# Power.net
KiCad netlist of a schematic drawn in Altium Designer
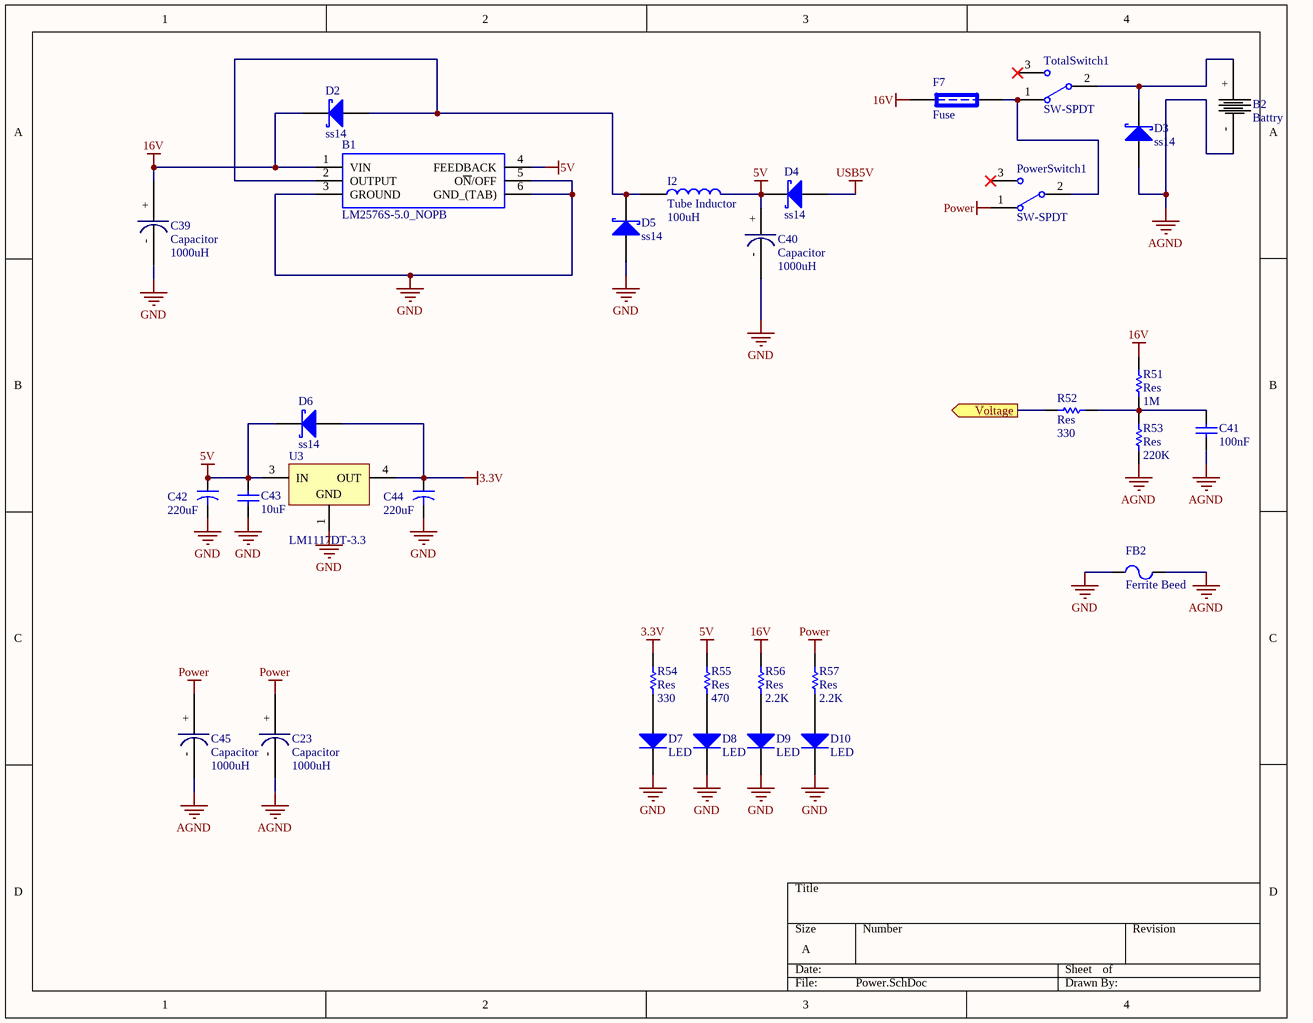
[diagram p0: Power.SchDoc]

(export (version "E")
  (design (tool "Eeschema 10.0.6"))
  (components
    (comp (ref "B1")
      (value "LM2576S-5.0_NOPB")
      (footprint "TO170P1435X465-6N")
      (description "SIMPLE SWITCHER 40V, 3A Low Component Count Step-Down Regulator")
      (fields
        (field (name "RS PART NUMBER") "5333226P")
        (field (name "MANUFACTURER_PART_NUMBER") "LM2576S-5.0/NOPB")
      )
      (libsource (lib "SSL_Power") (part "LM2576S-5.0_NOPB"))
    )
    (comp (ref "B2") (value "Battry") (footprint "Battry") (libsource (lib "SSL_Power") (part "Battry")))
    (comp (ref "C23")
      (value "Capacitor")
      (footprint "DIPCap")
      (fields (field (name "CAPACITANCE") "1000uH"))
      (libsource (lib "SSL_Power") (part "DIPCap"))
    )
    (comp (ref "C39")
      (value "Capacitor")
      (footprint "DIPCap")
      (fields (field (name "CAPACITANCE") "1000uH"))
      (libsource (lib "SSL_Power") (part "DIPCap"))
    )
    (comp (ref "C40")
      (value "Capacitor")
      (footprint "DIPCap")
      (fields (field (name "CAPACITANCE") "1000uH"))
      (libsource (lib "SSL_Power") (part "DIPCap"))
    )
    (comp (ref "C41")
      (value "100nF")
      (footprint "2012[0805]")
      (description "Capacitor")
      (fields (field (name "Comment") "Cap_UP") (field (name "PUBLISHER") "Altium Limited"))
      (libsource (lib "KN2CLib") (part "Cap_UP"))
    )
    (comp (ref "C42")
      (value "220uF")
      (footprint "7343")
      (description "Capacitor")
      (fields (field (name "Comment") "Cap_El") (field (name "PUBLISHER") "Altium Limited"))
      (libsource (lib "KN2CLib") (part "Cap_El"))
    )
    (comp (ref "C43")
      (value "10uF")
      (footprint "2012[0805]")
      (description "Capacitor")
      (fields (field (name "Comment") "Cap_UP") (field (name "PUBLISHER") "Altium Limited"))
      (libsource (lib "KN2CLib") (part "Cap_UP"))
    )
    (comp (ref "C44")
      (value "220uF")
      (footprint "7343")
      (description "Capacitor")
      (fields (field (name "Comment") "Cap_El") (field (name "PUBLISHER") "Altium Limited"))
      (libsource (lib "KN2CLib") (part "Cap_El"))
    )
    (comp (ref "C45")
      (value "Capacitor")
      (footprint "DIPCap")
      (fields (field (name "CAPACITANCE") "1000uH"))
      (libsource (lib "SSL_Power") (part "DIPCap"))
    )
    (comp (ref "D2")
      (value "ss14")
      (footprint "US1m")
      (description "Schottky Diode")
      (fields (field (name "PUBLISHER") "Altium Limited"))
      (libsource (lib "Miscellaneous Devices") (part "D Schottky"))
    )
    (comp (ref "D3")
      (value "ss14")
      (footprint "US1m")
      (description "Schottky Diode")
      (fields (field (name "PUBLISHER") "Altium Limited"))
      (libsource (lib "Miscellaneous Devices") (part "D Schottky"))
    )
    (comp (ref "D4")
      (value "ss14")
      (footprint "US1m")
      (description "Schottky Diode")
      (fields (field (name "PUBLISHER") "Altium Limited"))
      (libsource (lib "Miscellaneous Devices") (part "D Schottky"))
    )
    (comp (ref "D5")
      (value "ss14")
      (footprint "US1m")
      (description "Schottky Diode")
      (fields (field (name "PUBLISHER") "Altium Limited"))
      (libsource (lib "Miscellaneous Devices") (part "D Schottky"))
    )
    (comp (ref "D6")
      (value "ss14")
      (footprint "US1m")
      (description "Schottky Diode")
      (fields (field (name "PUBLISHER") "Altium Limited"))
      (libsource (lib "Miscellaneous Devices") (part "D Schottky"))
    )
    (comp (ref "D7")
      (value "LED")
      (footprint "2012[0805]")
      (description "1 Amp General Purpose Rectifier")
      (fields (field (name "PUBLISHER") "Altium Limited"))
      (libsource (lib "KN2CLib") (part "Diode"))
    )
    (comp (ref "D8")
      (value "LED")
      (footprint "2012[0805]")
      (description "1 Amp General Purpose Rectifier")
      (fields (field (name "PUBLISHER") "Altium Limited"))
      (libsource (lib "KN2CLib") (part "Diode"))
    )
    (comp (ref "D9")
      (value "LED")
      (footprint "2012[0805]")
      (description "1 Amp General Purpose Rectifier")
      (fields (field (name "PUBLISHER") "Altium Limited"))
      (libsource (lib "KN2CLib") (part "Diode"))
    )
    (comp (ref "D10")
      (value "LED")
      (footprint "2012[0805]")
      (description "1 Amp General Purpose Rectifier")
      (fields (field (name "PUBLISHER") "Altium Limited"))
      (libsource (lib "KN2CLib") (part "Diode"))
    )
    (comp (ref "F7")
      (value "Fuse")
      (footprint "3216[1206]")
      (fields (field (name "PUBLISHER") "Altium Limited"))
      (libsource (lib "KN2CLib") (part "Fuse"))
    )
    (comp (ref "FB2")
      (value "Ferrite Beed")
      (footprint "3216[1206]")
      (fields (field (name "PUBLISHER") "Altium Limited"))
      (libsource (lib "KN2CLib") (part "Ferrite Beed"))
    )
    (comp (ref "I2")
      (value "Tube Inductor")
      (footprint "Tube_Inductor")
      (fields (field (name "INDUCTANCE") "100uH"))
      (libsource (lib "SSL_Power") (part "Tube_Inductor"))
    )
    (comp (ref "PowerSwitch1")
      (value "SW-SPDT")
      (footprint "KEYKHRAB")
      (description "SPDT Subminiature Toggle Switch, Right Angle Mounting, Vertical Actuation")
      (fields (field (name "PUBLISHER") "Altium Limited"))
      (libsource (lib "KN2CLib") (part "SW-SPDT"))
    )
    (comp (ref "R51")
      (value "Res")
      (footprint "2012[0805]")
      (description "Semiconductor Resistor")
      (fields (field (name "ALTIUM_VALUE") "1M") (field (name "PUBLISHER") "Altium Limited"))
      (libsource (lib "KN2CLib") (part "Res"))
    )
    (comp (ref "R52")
      (value "Res")
      (footprint "2012[0805]")
      (description "Semiconductor Resistor")
      (fields (field (name "ALTIUM_VALUE") "330") (field (name "PUBLISHER") "Altium Limited"))
      (libsource (lib "KN2CLib") (part "Res"))
    )
    (comp (ref "R53")
      (value "Res")
      (footprint "2012[0805]")
      (description "Semiconductor Resistor")
      (fields (field (name "ALTIUM_VALUE") "220K") (field (name "PUBLISHER") "Altium Limited"))
      (libsource (lib "KN2CLib") (part "Res"))
    )
    (comp (ref "R54")
      (value "Res")
      (footprint "2012[0805]")
      (description "Semiconductor Resistor")
      (fields (field (name "ALTIUM_VALUE") "330") (field (name "PUBLISHER") "Altium Limited"))
      (libsource (lib "KN2CLib") (part "Res"))
    )
    (comp (ref "R55")
      (value "Res")
      (footprint "2012[0805]")
      (description "Semiconductor Resistor")
      (fields (field (name "ALTIUM_VALUE") "470") (field (name "PUBLISHER") "Altium Limited"))
      (libsource (lib "KN2CLib") (part "Res"))
    )
    (comp (ref "R56")
      (value "Res")
      (footprint "2012[0805]")
      (description "Semiconductor Resistor")
      (fields (field (name "ALTIUM_VALUE") "2.2K") (field (name "PUBLISHER") "Altium Limited"))
      (libsource (lib "KN2CLib") (part "Res"))
    )
    (comp (ref "R57")
      (value "Res")
      (footprint "2012[0805]")
      (description "Semiconductor Resistor")
      (fields (field (name "ALTIUM_VALUE") "2.2K") (field (name "PUBLISHER") "Altium Limited"))
      (libsource (lib "KN2CLib") (part "Res"))
    )
    (comp (ref "TotalSwitch1")
      (value "SW-SPDT")
      (footprint "KEYKHRAB")
      (description "SPDT Subminiature Toggle Switch, Right Angle Mounting, Vertical Actuation")
      (fields (field (name "PUBLISHER") "Altium Limited"))
      (libsource (lib "KN2CLib") (part "SW-SPDT"))
    )
    (comp (ref "U3")
      (value "LM1117DT-3.3")
      (footprint "SOT223")
      (description "800mA Low-Dropout Linear Regulator, 3-pin TO-252")
      (fields
        (field (name "MANUFACTURER") "National Semiconductor")
        (field (name "PUBLISHER") "Altium Limited")
      )
      (libsource (lib "NSC LDO") (part "LM1117DT-3.3"))
    )
  )
  (nets
    (net (code "1") (name "/Voltage") (class "Default")
      (node (ref "R52") (pin "1") (pinfunction "1_1") (pintype "passive"))
    )
    (net (code "2") (name "3.3V") (class "Default")
      (node (ref "C44") (pin "1") (pinfunction "1_1") (pintype "passive"))
      (node (ref "D6") (pin "1") (pinfunction "A_1") (pintype "passive"))
      (node (ref "R54") (pin "2") (pinfunction "2_2") (pintype "passive"))
      (node (ref "U3") (pin "4") (pinfunction "OUT_4") (pintype "power_in"))
    )
    (net (code "3") (name "5V") (class "Default")
      (node (ref "B1") (pin "4") (pinfunction "FEEDBACK_4") (pintype "passive"))
      (node (ref "C40") (pin "+") (pinfunction "+_+") (pintype "passive"))
      (node (ref "C42") (pin "1") (pinfunction "1_1") (pintype "passive"))
      (node (ref "C43") (pin "2") (pinfunction "2_2") (pintype "passive"))
      (node (ref "D4") (pin "2") (pinfunction "K_2") (pintype "passive"))
      (node (ref "D6") (pin "2") (pinfunction "K_2") (pintype "passive"))
      (node (ref "I2") (pin "1") (pinfunction "1_1") (pintype "passive"))
      (node (ref "R55") (pin "2") (pinfunction "2_2") (pintype "passive"))
      (node (ref "U3") (pin "3") (pinfunction "IN_3") (pintype "power_in"))
    )
    (net (code "4") (name "16V") (class "Default")
      (node (ref "B1") (pin "1") (pinfunction "VIN_1") (pintype "passive"))
      (node (ref "C39") (pin "+") (pinfunction "+_+") (pintype "passive"))
      (node (ref "D2") (pin "2") (pinfunction "K_2") (pintype "passive"))
      (node (ref "F7") (pin "1") (pinfunction "1_1") (pintype "passive"))
      (node (ref "R51") (pin "2") (pinfunction "2_2") (pintype "passive"))
      (node (ref "R56") (pin "2") (pinfunction "2_2") (pintype "passive"))
    )
    (net (code "5") (name "AGND") (class "Default")
      (node (ref "B2") (pin "-") (pinfunction "-_-") (pintype "passive"))
      (node (ref "C23") (pin "-") (pinfunction "-_-") (pintype "passive"))
      (node (ref "C41") (pin "1") (pinfunction "1_1") (pintype "passive"))
      (node (ref "C45") (pin "-") (pinfunction "-_-") (pintype "passive"))
      (node (ref "D3") (pin "1") (pinfunction "A_1") (pintype "passive"))
      (node (ref "FB2") (pin "2") (pinfunction "2_2") (pintype "passive"))
      (node (ref "R53") (pin "1") (pinfunction "1_1") (pintype "passive"))
    )
    (net (code "6") (name "GND") (class "Default")
      (node (ref "B1") (pin "3") (pinfunction "GROUND_3") (pintype "passive"))
      (node (ref "B1") (pin "5") (pinfunction "O~{N}/OFF_5") (pintype "passive"))
      (node (ref "B1") (pin "6") (pinfunction "GND_(TAB)_6") (pintype "passive"))
      (node (ref "C39") (pin "-") (pinfunction "-_-") (pintype "passive"))
      (node (ref "C40") (pin "-") (pinfunction "-_-") (pintype "passive"))
      (node (ref "C42") (pin "2") (pinfunction "2_2") (pintype "passive"))
      (node (ref "C43") (pin "1") (pinfunction "1_1") (pintype "passive"))
      (node (ref "C44") (pin "2") (pinfunction "2_2") (pintype "passive"))
      (node (ref "D10") (pin "2") (pinfunction "K_2") (pintype "passive"))
      (node (ref "D5") (pin "1") (pinfunction "A_1") (pintype "passive"))
      (node (ref "D7") (pin "2") (pinfunction "K_2") (pintype "passive"))
      (node (ref "D8") (pin "2") (pinfunction "K_2") (pintype "passive"))
      (node (ref "D9") (pin "2") (pinfunction "K_2") (pintype "passive"))
      (node (ref "FB2") (pin "1") (pinfunction "1_1") (pintype "passive"))
      (node (ref "U3") (pin "1") (pinfunction "GND_1") (pintype "power_in"))
    )
    (net (code "7") (name "Net-(B1-OUTPUT)") (class "Default")
      (node (ref "B1") (pin "2") (pinfunction "OUTPUT_2") (pintype "passive"))
      (node (ref "D2") (pin "1") (pinfunction "A_1") (pintype "passive"))
      (node (ref "D5") (pin "2") (pinfunction "K_2") (pintype "passive"))
      (node (ref "I2") (pin "0") (pinfunction "0_0") (pintype "passive"))
    )
    (net (code "8") (name "Net-(C41-Pad2)") (class "Default")
      (node (ref "C41") (pin "2") (pinfunction "2_2") (pintype "passive"))
      (node (ref "R51") (pin "1") (pinfunction "1_1") (pintype "passive"))
      (node (ref "R52") (pin "2") (pinfunction "2_2") (pintype "passive"))
      (node (ref "R53") (pin "2") (pinfunction "2_2") (pintype "passive"))
    )
    (net (code "9") (name "Net-(D3-K)") (class "Default")
      (node (ref "B2") (pin "+") (pinfunction "+_+") (pintype "passive"))
      (node (ref "D3") (pin "2") (pinfunction "K_2") (pintype "passive"))
      (node (ref "TotalSwitch1") (pin "2") (pinfunction "2_2") (pintype "passive"))
    )
    (net (code "10") (name "Net-(D7-A)") (class "Default")
      (node (ref "D7") (pin "1") (pinfunction "A_1") (pintype "passive"))
      (node (ref "R54") (pin "1") (pinfunction "1_1") (pintype "passive"))
    )
    (net (code "11") (name "Net-(D8-A)") (class "Default")
      (node (ref "D8") (pin "1") (pinfunction "A_1") (pintype "passive"))
      (node (ref "R55") (pin "1") (pinfunction "1_1") (pintype "passive"))
    )
    (net (code "12") (name "Net-(D9-A)") (class "Default")
      (node (ref "D9") (pin "1") (pinfunction "A_1") (pintype "passive"))
      (node (ref "R56") (pin "1") (pinfunction "1_1") (pintype "passive"))
    )
    (net (code "13") (name "Net-(D10-A)") (class "Default")
      (node (ref "D10") (pin "1") (pinfunction "A_1") (pintype "passive"))
      (node (ref "R57") (pin "1") (pinfunction "1_1") (pintype "passive"))
    )
    (net (code "14") (name "Net-(TotalSwitch1-3)") (class "Default")
      (node (ref "F7") (pin "2") (pinfunction "2_2") (pintype "passive"))
      (node (ref "PowerSwitch1") (pin "2") (pinfunction "2_2") (pintype "passive"))
      (node (ref "TotalSwitch1") (pin "1") (pinfunction "3_1") (pintype "passive"))
    )
    (net (code "15") (name "Power") (class "Default")
      (node (ref "C23") (pin "+") (pinfunction "+_+") (pintype "passive"))
      (node (ref "C45") (pin "+") (pinfunction "+_+") (pintype "passive"))
      (node (ref "PowerSwitch1") (pin "1") (pinfunction "3_1") (pintype "passive"))
      (node (ref "R57") (pin "2") (pinfunction "2_2") (pintype "passive"))
    )
    (net (code "16") (name "USB5V") (class "Default")
      (node (ref "D4") (pin "1") (pinfunction "A_1") (pintype "passive"))
    )
    (net (code "17") (name "unconnected-(PowerSwitch1-1-Pad3)") (class "Default")
      (node (ref "PowerSwitch1") (pin "3") (pinfunction "1_3") (pintype "passive+no_connect"))
    )
    (net (code "18") (name "unconnected-(TotalSwitch1-1-Pad3)") (class "Default")
      (node (ref "TotalSwitch1") (pin "3") (pinfunction "1_3") (pintype "passive+no_connect"))
    )
  )
)
